# Control_board_Page_4.net
KiCad netlist of a schematic drawn in Altium Designer
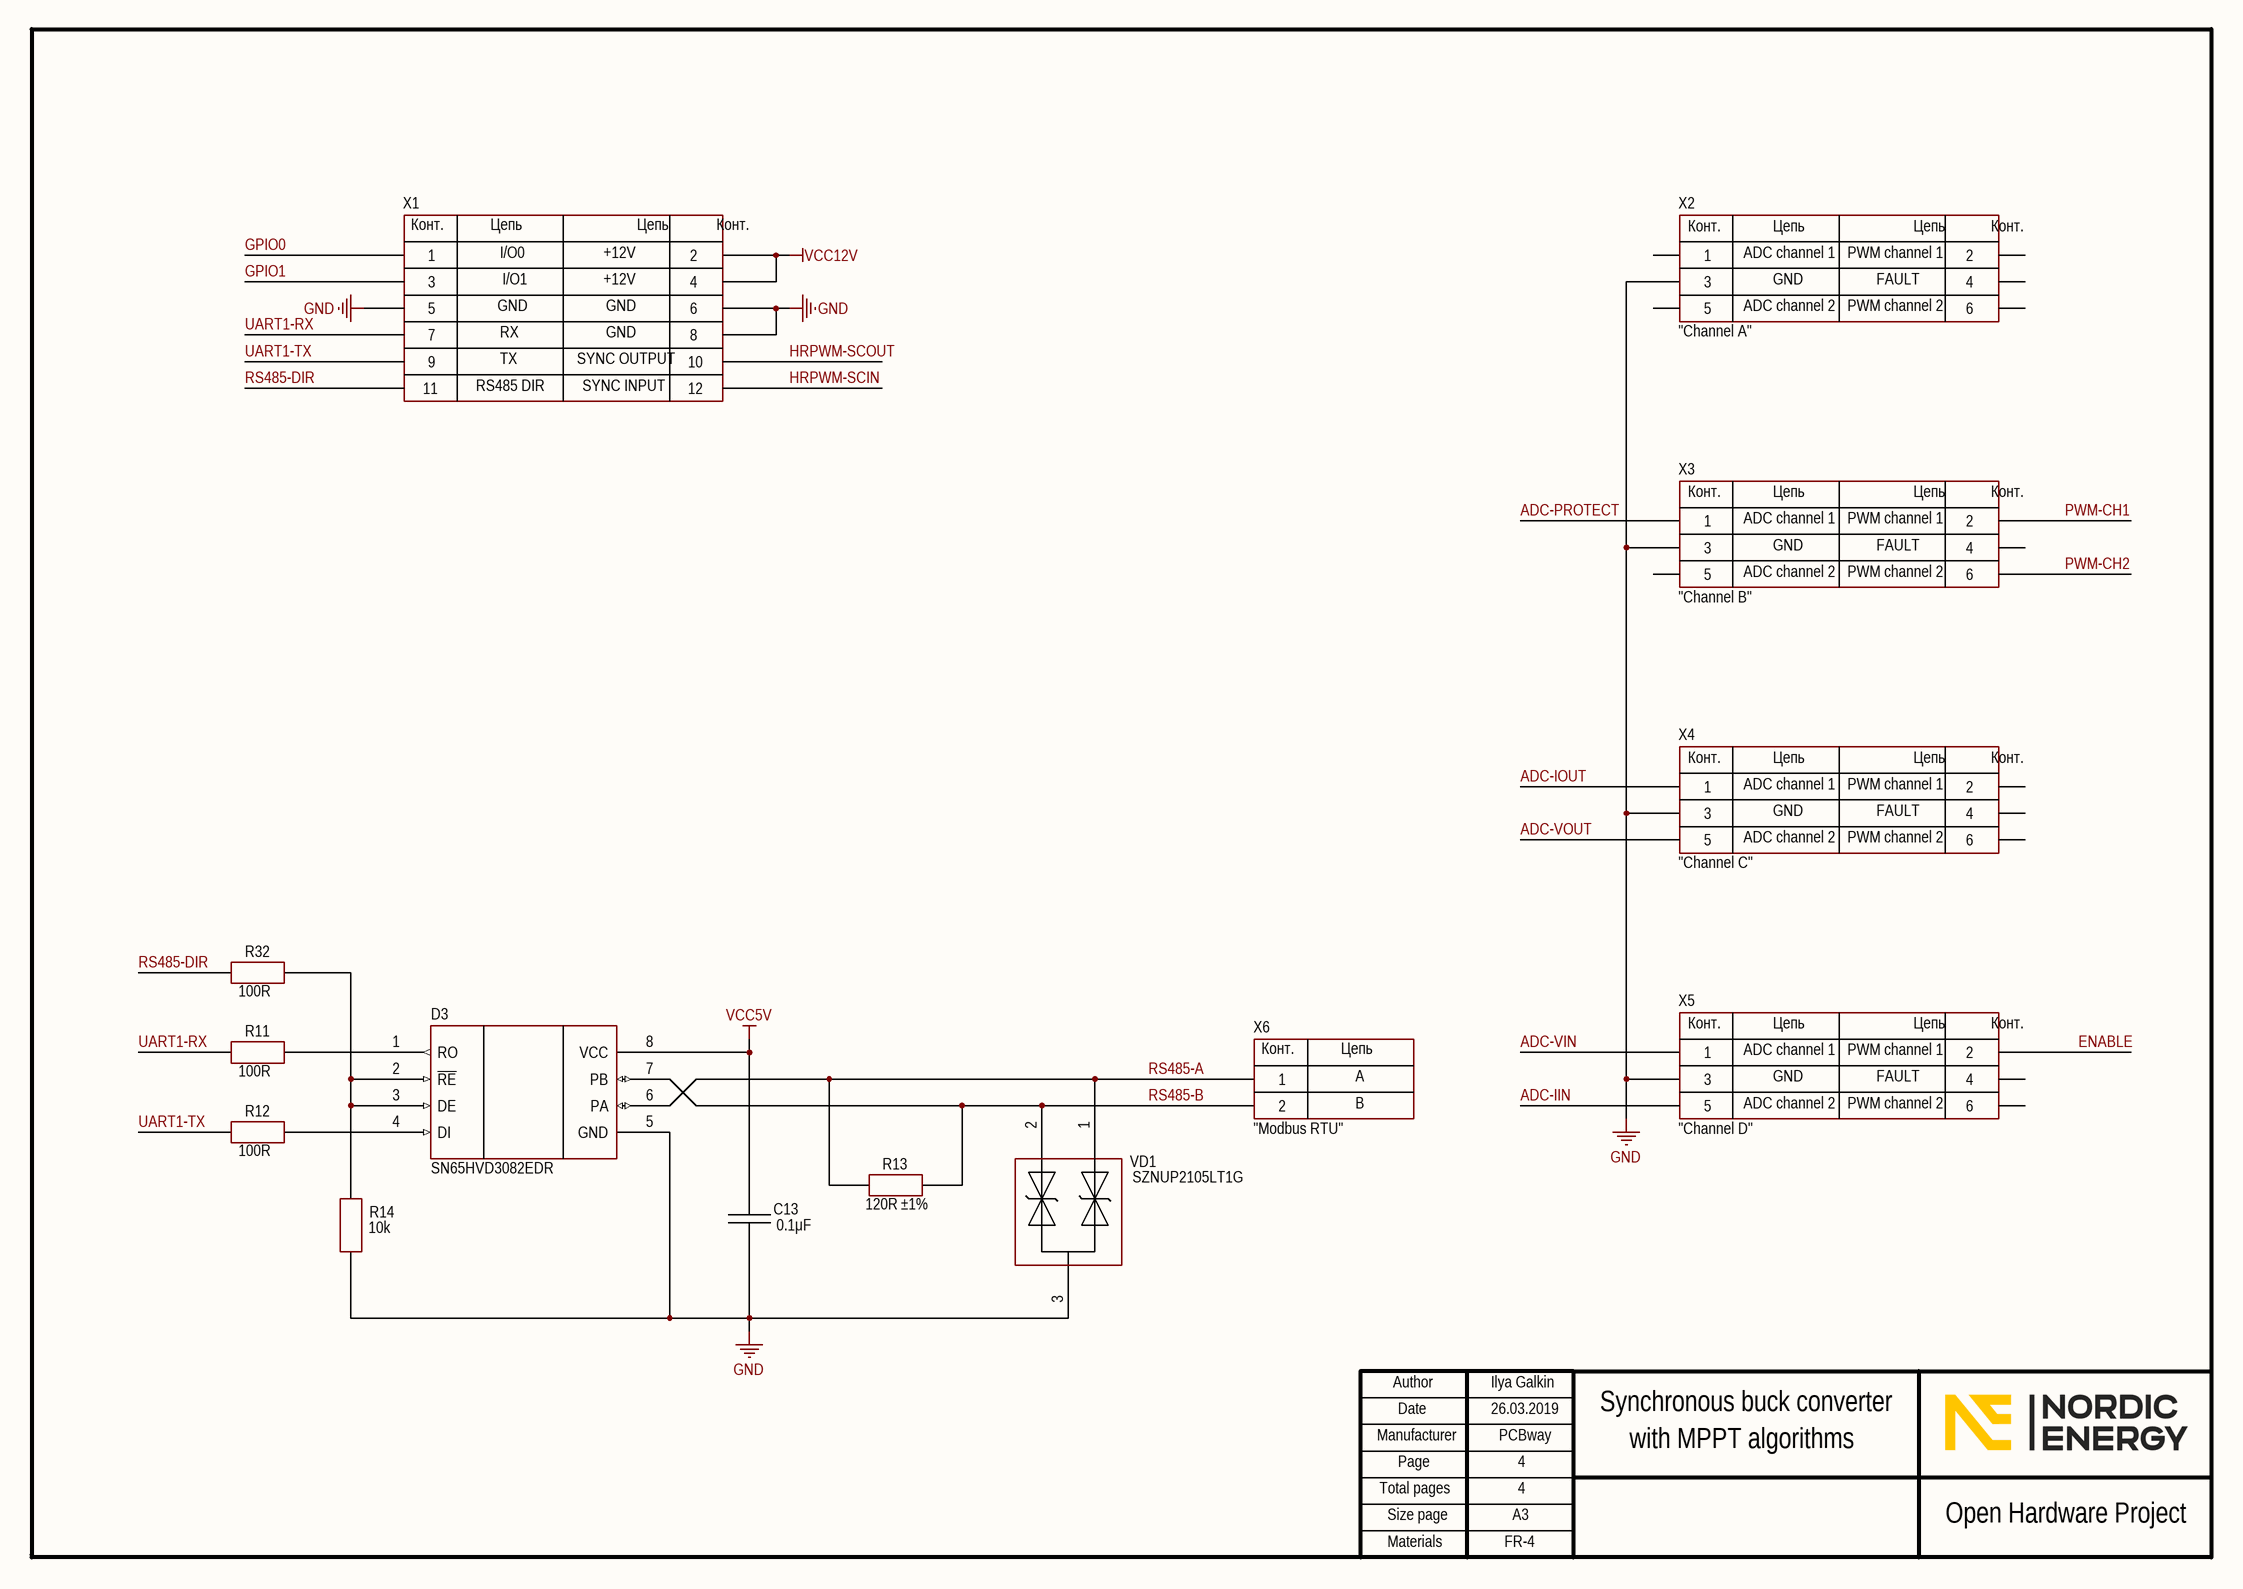
[diagram p0: Control board. Page 4.SchDoc]

(export (version "E")
  (design (tool "Eeschema 10.0.6"))
  (components
    (comp (ref "C13")
      (value "0.1μF")
      (footprint "CH0805C")
      (fields (field (name "MANUFACTURER") "Yageo"))
      (libsource (lib "Discrete") (part "Capacitor"))
    )
    (comp (ref "D3")
      (value "SN65HVD3082EDR")
      (footprint "8-SOIC")
      (description "RS485")
      (fields (field (name "MANUFACTURER") "Texas Instruments"))
      (libsource (lib "Interface") (part "SN65HVD3082EDR"))
    )
    (comp (ref "R11")
      (value "100R")
      (footprint "CH0805R")
      (fields (field (name "MANUFACTURER") "Yageo"))
      (libsource (lib "Discrete") (part "Resistor"))
    )
    (comp (ref "R12")
      (value "100R")
      (footprint "CH0805R")
      (fields (field (name "MANUFACTURER") "Yageo"))
      (libsource (lib "Discrete") (part "Resistor"))
    )
    (comp (ref "R13")
      (value "120R")
      (footprint "CH0805R")
      (fields (field (name "MANUFACTURER") "Yageo") (field (name "COMPONENTKIND") "±1%"))
      (libsource (lib "") (part "Resistor_2"))
    )
    (comp (ref "R14")
      (value "10k")
      (footprint "CH0805R")
      (fields (field (name "MANUFACTURER") "Yageo"))
      (libsource (lib "") (part "Resistor_1"))
    )
    (comp (ref "R32")
      (value "100R")
      (footprint "CH0805R")
      (fields (field (name "MANUFACTURER") "Yageo"))
      (libsource (lib "Discrete") (part "Resistor"))
    )
    (comp (ref "VD1")
      (value "SZNUP2105LT1G")
      (footprint "SOT23_132")
      (fields (field (name "MANUFACTURER") "ON Semiconductor"))
      (libsource (lib "Diods") (part "TVS Array"))
    )
    (comp (ref "X1")
      (value "*")
      (footprint "CON: PBD-12")
      (libsource (lib "Connectors") (part "12-Connector (2)"))
    )
    (comp (ref "X2")
      (value "\"Channel A\"")
      (footprint "CON: PBD-6")
      (libsource (lib "Connectors") (part "6(2)-Connector"))
    )
    (comp (ref "X3")
      (value "\"Channel B\"")
      (footprint "CON: PBD-6")
      (libsource (lib "Connectors") (part "6(2)-Connector"))
    )
    (comp (ref "X4")
      (value "\"Channel C\"")
      (footprint "CON: PBD-6")
      (libsource (lib "Connectors") (part "6(2)-Connector"))
    )
    (comp (ref "X5")
      (value "\"Channel D\"")
      (footprint "CON: PBD-6")
      (libsource (lib "Connectors") (part "6(2)-Connector"))
    )
    (comp (ref "X6")
      (value "\"Modbus RTU\"")
      (footprint "CON: 0395430002 (5 mm)")
      (fields (field (name "MANUFACTURER") "Molex"))
      (libsource (lib "Connectors") (part "2-Connector"))
    )
  )
  (nets
    (net (code "1") (name "/ADC-IIN") (class "Default")
      (node (ref "X5") (pin "5") (pinfunction "5_5") (pintype "power_in"))
    )
    (net (code "2") (name "/ADC-IOUT") (class "Default")
      (node (ref "X4") (pin "1") (pinfunction "1_1") (pintype "passive"))
    )
    (net (code "3") (name "/ADC-PROTECT") (class "Default")
      (node (ref "X3") (pin "1") (pinfunction "1_1") (pintype "passive"))
    )
    (net (code "4") (name "/ADC-VIN") (class "Default")
      (node (ref "X5") (pin "1") (pinfunction "1_1") (pintype "passive"))
    )
    (net (code "5") (name "/ADC-VOUT") (class "Default")
      (node (ref "X4") (pin "5") (pinfunction "5_5") (pintype "power_in"))
    )
    (net (code "6") (name "/ENABLE") (class "Default")
      (node (ref "X5") (pin "2") (pinfunction "2_2") (pintype "passive"))
    )
    (net (code "7") (name "/GPIO0") (class "Default")
      (node (ref "X1") (pin "1") (pinfunction "1_1") (pintype "passive"))
    )
    (net (code "8") (name "/GPIO1") (class "Default")
      (node (ref "X1") (pin "3") (pinfunction "3_3") (pintype "power_in"))
    )
    (net (code "9") (name "/HRPWM-SCIN") (class "Default")
      (node (ref "X1") (pin "12") (pinfunction "12_12") (pintype "power_in"))
    )
    (net (code "10") (name "/HRPWM-SCOUT") (class "Default")
      (node (ref "X1") (pin "10") (pinfunction "10_10") (pintype "power_in"))
    )
    (net (code "11") (name "/PWM-CH1") (class "Default")
      (node (ref "X3") (pin "2") (pinfunction "2_2") (pintype "passive"))
    )
    (net (code "12") (name "/PWM-CH2") (class "Default")
      (node (ref "X3") (pin "6") (pinfunction "6_6") (pintype "power_in"))
    )
    (net (code "13") (name "/RS485-A") (class "Default")
      (node (ref "D3") (pin "6") (pinfunction "PA_6") (pintype "bidirectional"))
      (node (ref "R13") (pin "1") (pinfunction "1_1") (pintype "passive"))
      (node (ref "VD1") (pin "1") (pintype "passive"))
      (node (ref "X6") (pin "1") (pinfunction "1_1") (pintype "passive"))
    )
    (net (code "14") (name "/RS485-B") (class "Default")
      (node (ref "D3") (pin "7") (pinfunction "PB_7") (pintype "bidirectional"))
      (node (ref "R13") (pin "2") (pinfunction "2_2") (pintype "passive"))
      (node (ref "VD1") (pin "2") (pintype "passive"))
      (node (ref "X6") (pin "2") (pinfunction "2_2") (pintype "passive"))
    )
    (net (code "15") (name "/RS485-DIR") (class "Default")
      (node (ref "R32") (pin "2") (pinfunction "2_2") (pintype "passive"))
      (node (ref "X1") (pin "11") (pinfunction "11_11") (pintype "power_in"))
    )
    (net (code "16") (name "/UART1-RX") (class "Default")
      (node (ref "R11") (pin "2") (pinfunction "2_2") (pintype "passive"))
      (node (ref "X1") (pin "7") (pinfunction "7_7") (pintype "power_in"))
    )
    (net (code "17") (name "/UART1-TX") (class "Default")
      (node (ref "R12") (pin "2") (pinfunction "2_2") (pintype "passive"))
      (node (ref "X1") (pin "9") (pinfunction "9_9") (pintype "power_in"))
    )
    (net (code "18") (name "GND") (class "Default")
      (node (ref "C13") (pin "1") (pinfunction "1_1") (pintype "power_in"))
      (node (ref "D3") (pin "5") (pinfunction "GND_5") (pintype "power_in"))
      (node (ref "R14") (pin "1") (pinfunction "1_1") (pintype "passive"))
      (node (ref "VD1") (pin "3") (pintype "passive"))
      (node (ref "X1") (pin "5") (pinfunction "5_5") (pintype "power_in"))
      (node (ref "X1") (pin "6") (pinfunction "6_6") (pintype "power_in"))
      (node (ref "X1") (pin "8") (pinfunction "8_8") (pintype "power_in"))
      (node (ref "X2") (pin "3") (pinfunction "3_3") (pintype "passive"))
      (node (ref "X3") (pin "3") (pinfunction "3_3") (pintype "passive"))
      (node (ref "X4") (pin "3") (pinfunction "3_3") (pintype "passive"))
      (node (ref "X5") (pin "3") (pinfunction "3_3") (pintype "passive"))
    )
    (net (code "19") (name "Net-(D3-DE)") (class "Default")
      (node (ref "D3") (pin "2") (pinfunction "~{RE}_2") (pintype "input"))
      (node (ref "D3") (pin "3") (pinfunction "DE_3") (pintype "input"))
      (node (ref "R14") (pin "2") (pinfunction "2_2") (pintype "passive"))
      (node (ref "R32") (pin "1") (pinfunction "1_1") (pintype "passive"))
    )
    (net (code "20") (name "Net-(D3-DI)") (class "Default")
      (node (ref "D3") (pin "4") (pinfunction "DI_4") (pintype "input"))
      (node (ref "R12") (pin "1") (pinfunction "1_1") (pintype "passive"))
    )
    (net (code "21") (name "Net-(D3-RO)") (class "Default")
      (node (ref "D3") (pin "1") (pinfunction "RO_1") (pintype "output"))
      (node (ref "R11") (pin "1") (pinfunction "1_1") (pintype "passive"))
    )
    (net (code "22") (name "VCC5V") (class "Default")
      (node (ref "C13") (pin "2") (pinfunction "2_2") (pintype "power_in"))
      (node (ref "D3") (pin "8") (pinfunction "VCC_8") (pintype "power_in"))
    )
    (net (code "23") (name "VCC12V") (class "Default")
      (node (ref "X1") (pin "2") (pinfunction "2_2") (pintype "passive"))
      (node (ref "X1") (pin "4") (pinfunction "4_4") (pintype "power_in"))
    )
    (net (code "24") (name "unconnected-(X2-Pad1)") (class "Default")
      (node (ref "X2") (pin "1") (pinfunction "1_1") (pintype "passive"))
    )
    (net (code "25") (name "unconnected-(X2-Pad2)") (class "Default")
      (node (ref "X2") (pin "2") (pinfunction "2_2") (pintype "passive"))
    )
    (net (code "26") (name "unconnected-(X2-Pad4)") (class "Default")
      (node (ref "X2") (pin "4") (pinfunction "4_4") (pintype "passive"))
    )
    (net (code "27") (name "unconnected-(X2-Pad5)") (class "Default")
      (node (ref "X2") (pin "5") (pinfunction "5_5") (pintype "power_in"))
    )
    (net (code "28") (name "unconnected-(X2-Pad6)") (class "Default")
      (node (ref "X2") (pin "6") (pinfunction "6_6") (pintype "power_in"))
    )
    (net (code "29") (name "unconnected-(X3-Pad4)") (class "Default")
      (node (ref "X3") (pin "4") (pinfunction "4_4") (pintype "passive"))
    )
    (net (code "30") (name "unconnected-(X3-Pad5)") (class "Default")
      (node (ref "X3") (pin "5") (pinfunction "5_5") (pintype "power_in"))
    )
    (net (code "31") (name "unconnected-(X4-Pad2)") (class "Default")
      (node (ref "X4") (pin "2") (pinfunction "2_2") (pintype "passive"))
    )
    (net (code "32") (name "unconnected-(X4-Pad4)") (class "Default")
      (node (ref "X4") (pin "4") (pinfunction "4_4") (pintype "passive"))
    )
    (net (code "33") (name "unconnected-(X4-Pad6)") (class "Default")
      (node (ref "X4") (pin "6") (pinfunction "6_6") (pintype "power_in"))
    )
    (net (code "34") (name "unconnected-(X5-Pad4)") (class "Default")
      (node (ref "X5") (pin "4") (pinfunction "4_4") (pintype "passive"))
    )
    (net (code "35") (name "unconnected-(X5-Pad6)") (class "Default")
      (node (ref "X5") (pin "6") (pinfunction "6_6") (pintype "power_in"))
    )
  )
)
